# SCH_Hack-club-Card_2024-05-15.net
KiCad netlist of a schematic drawn in EasyEDA
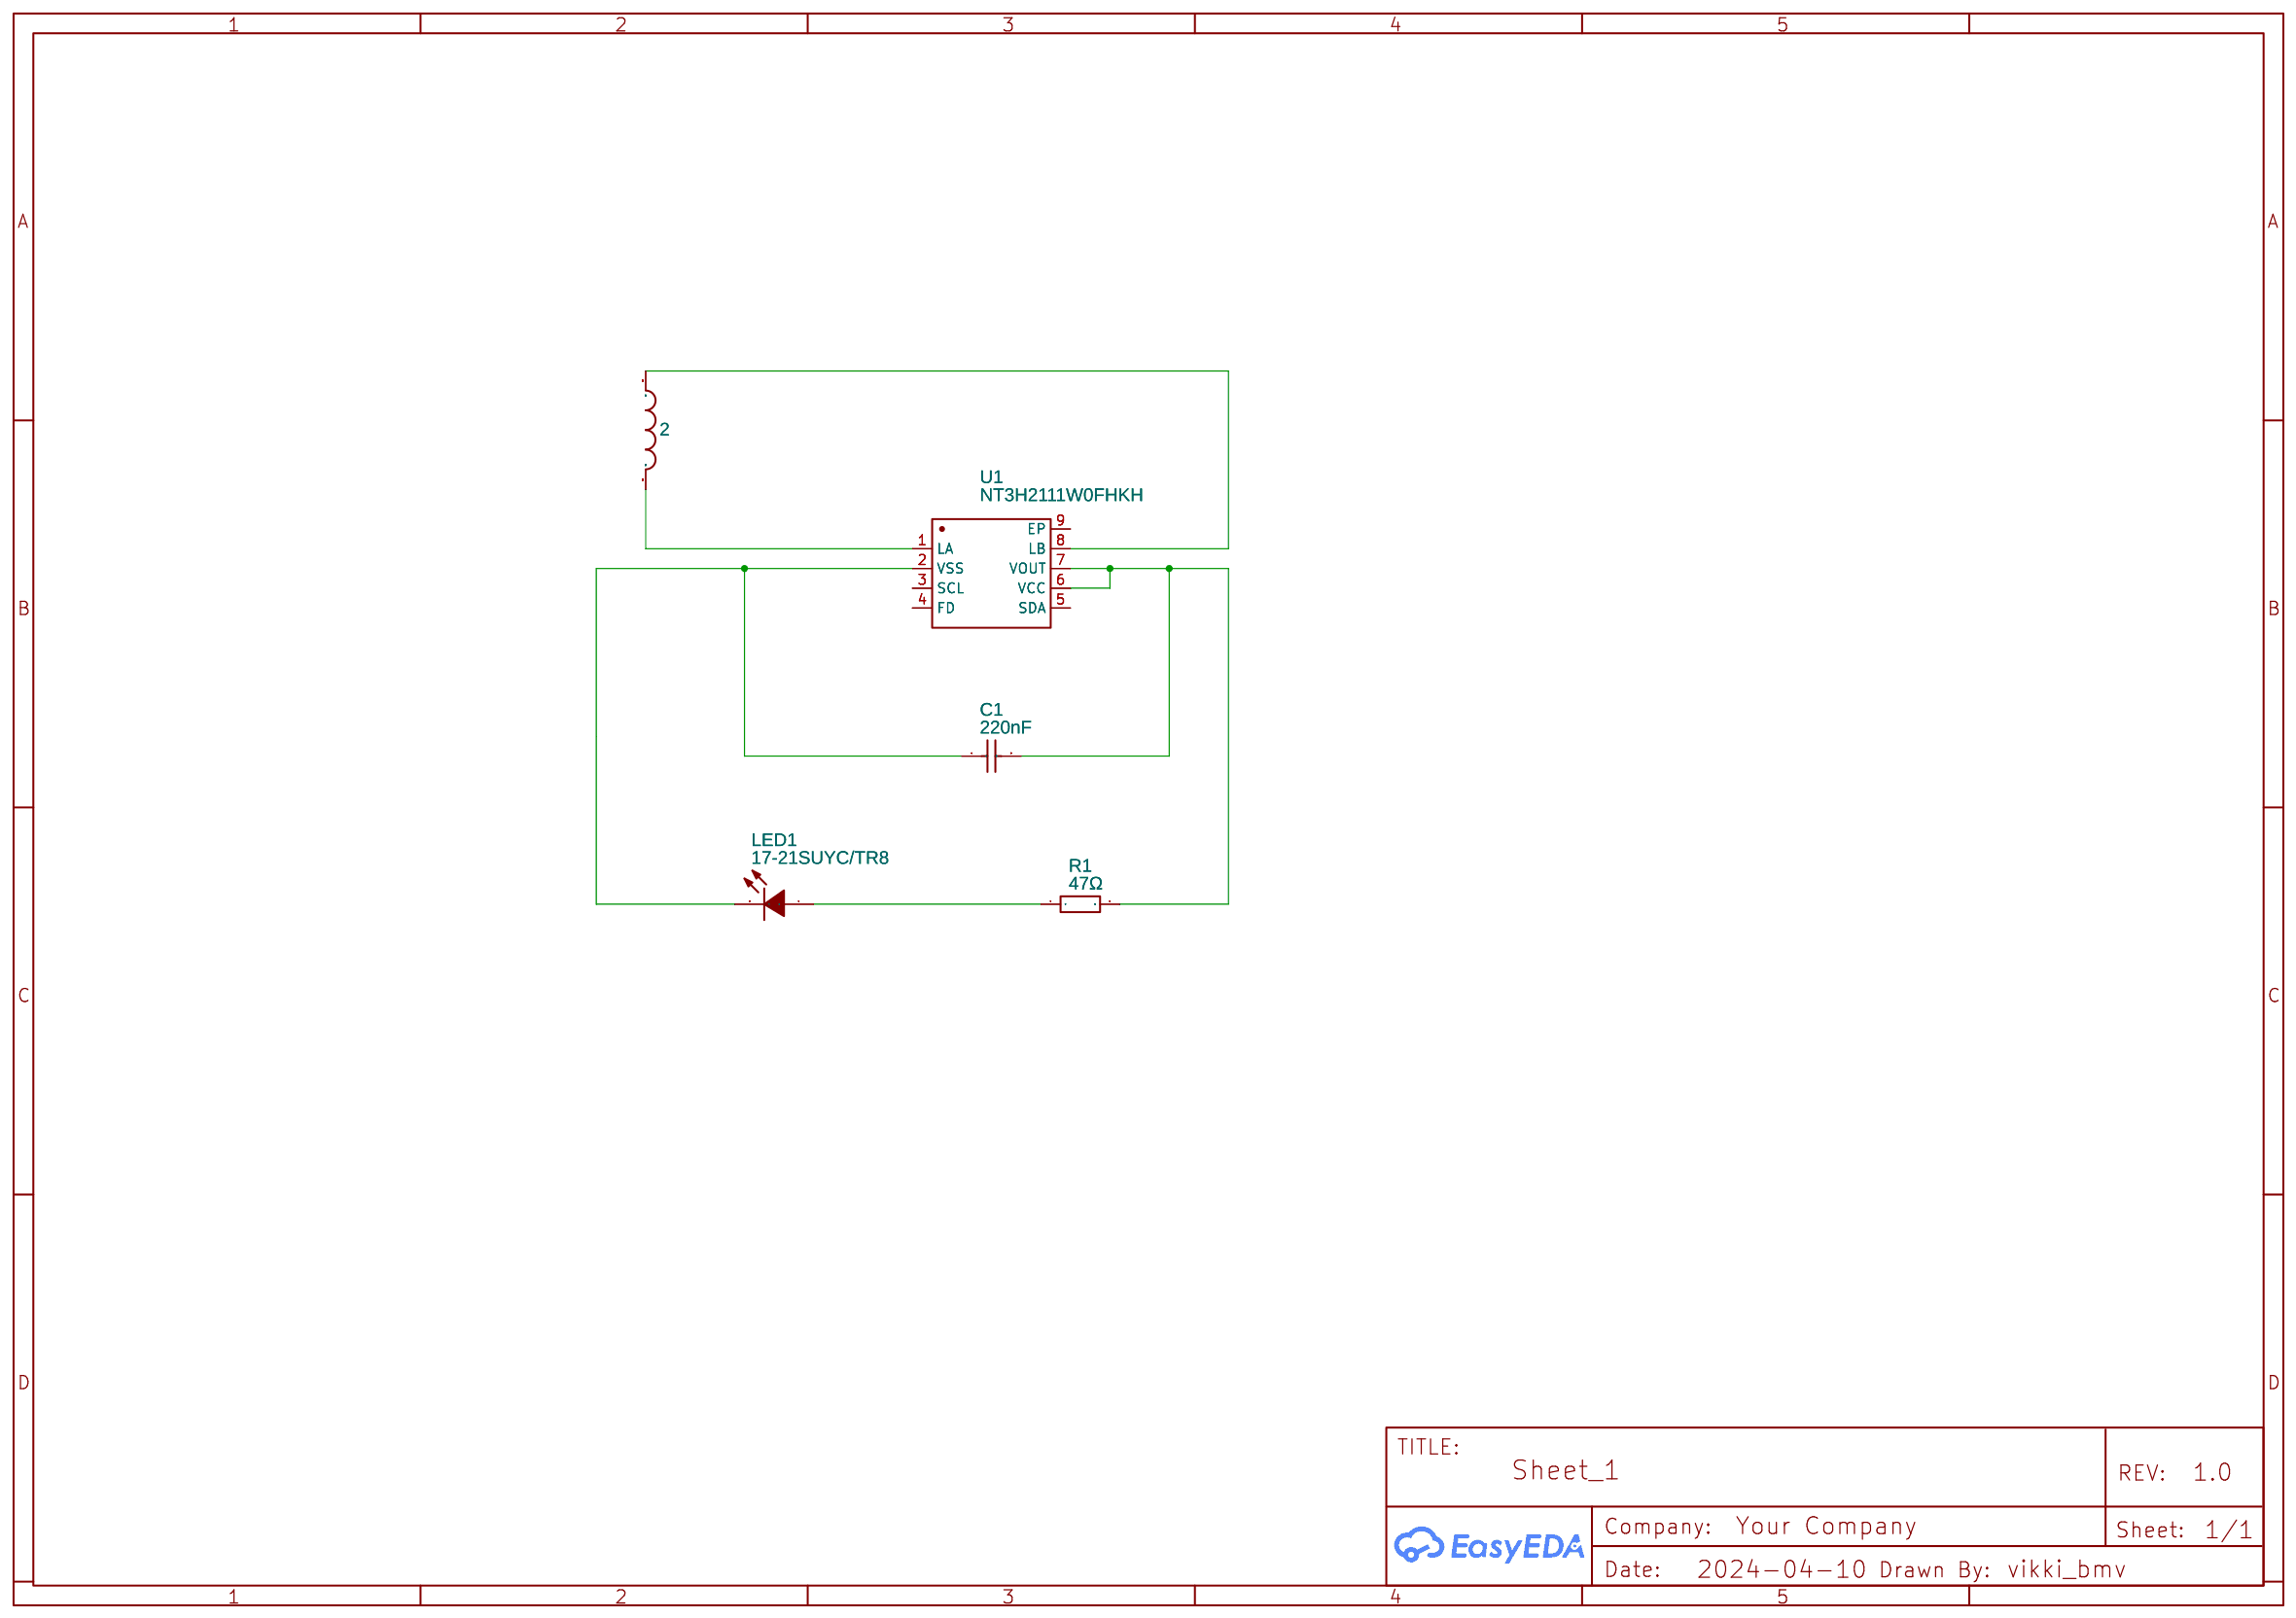
[diagram p0: schematic sheet]

(export (version "E")
  (design (tool "Eeschema 10.0.6"))
  (components
    (comp (ref "2") (value "25X48MM_NFC_ANTENNA") (libsource (lib "") (part "25X48MM_NFC_ANTENNA")))
    (comp (ref "C1")
      (value "220nF")
      (fields
        (field (name "Manufacturer Part") "CL10B224KA8NNNC")
        (field (name "Manufacturer") "SAMSUNG(三星)")
      )
      (libsource (lib "") (part "CL10B224KA8NNNC"))
    )
    (comp (ref "LED1")
      (value "17-21SUYC/TR8")
      (fields (field (name "Manufacturer Part") "KT-0805黄灯") (field (name "Manufacturer") "KENTO"))
      (libsource (lib "") (part "17-21SUYC/TR8"))
    )
    (comp (ref "R1")
      (value "47Ω")
      (fields
        (field (name "Manufacturer Part") "0603WAF470JT5E")
        (field (name "Manufacturer") "UNI-ROYAL(厚声)")
      )
      (libsource (lib "") (part "0603WAF470JT5E"))
    )
    (comp (ref "U1")
      (value "NT3H2111W0FHKH")
      (fields (field (name "Manufacturer") "NXP(恩智浦)"))
      (libsource (lib "") (part "NT3H2111W0FHKH"))
    )
  )
  (nets
    (net (code "1") (name "Net-(LED1-+)") (class "Default")
      (node (ref "LED1") (pin "1") (pinfunction "+_1") (pintype "unspecified"))
      (node (ref "R1") (pin "1") (pinfunction "1_1") (pintype "input"))
    )
    (net (code "2") (name "Net-(LED1--)") (class "Default")
      (node (ref "C1") (pin "1") (pinfunction "1_1") (pintype "input"))
      (node (ref "LED1") (pin "2") (pinfunction "-_2") (pintype "unspecified"))
      (node (ref "U1") (pin "2") (pinfunction "VSS_2") (pintype "unspecified"))
    )
    (net (code "3") (name "Net-(U1-LA)") (class "Default")
      (node (ref "2") (pin "P$2") (pinfunction "P$2_P$2") (pintype "bidirectional"))
      (node (ref "U1") (pin "1") (pinfunction "LA_1") (pintype "unspecified"))
    )
    (net (code "4") (name "Net-(U1-LB)") (class "Default")
      (node (ref "2") (pin "P$1") (pinfunction "P$1_P$1") (pintype "bidirectional"))
      (node (ref "U1") (pin "8") (pinfunction "LB_8") (pintype "unspecified"))
    )
    (net (code "5") (name "Net-(U1-VCC)") (class "Default")
      (node (ref "C1") (pin "2") (pinfunction "2_2") (pintype "input"))
      (node (ref "R1") (pin "2") (pinfunction "2_2") (pintype "input"))
      (node (ref "U1") (pin "6") (pinfunction "VCC_6") (pintype "unspecified"))
      (node (ref "U1") (pin "7") (pinfunction "VOUT_7") (pintype "unspecified"))
    )
    (net (code "6") (name "unconnected-(U1-EP-Pad9)") (class "Default")
      (node (ref "U1") (pin "9") (pinfunction "EP_9") (pintype "unspecified"))
    )
    (net (code "7") (name "unconnected-(U1-FD-Pad4)") (class "Default")
      (node (ref "U1") (pin "4") (pinfunction "FD_4") (pintype "unspecified"))
    )
    (net (code "8") (name "unconnected-(U1-SCL-Pad3)") (class "Default")
      (node (ref "U1") (pin "3") (pinfunction "SCL_3") (pintype "unspecified"))
    )
    (net (code "9") (name "unconnected-(U1-SDA-Pad5)") (class "Default")
      (node (ref "U1") (pin "5") (pinfunction "SDA_5") (pintype "unspecified"))
    )
  )
)
